# pihat.net
KiCad netlist of a schematic drawn in EAGLE
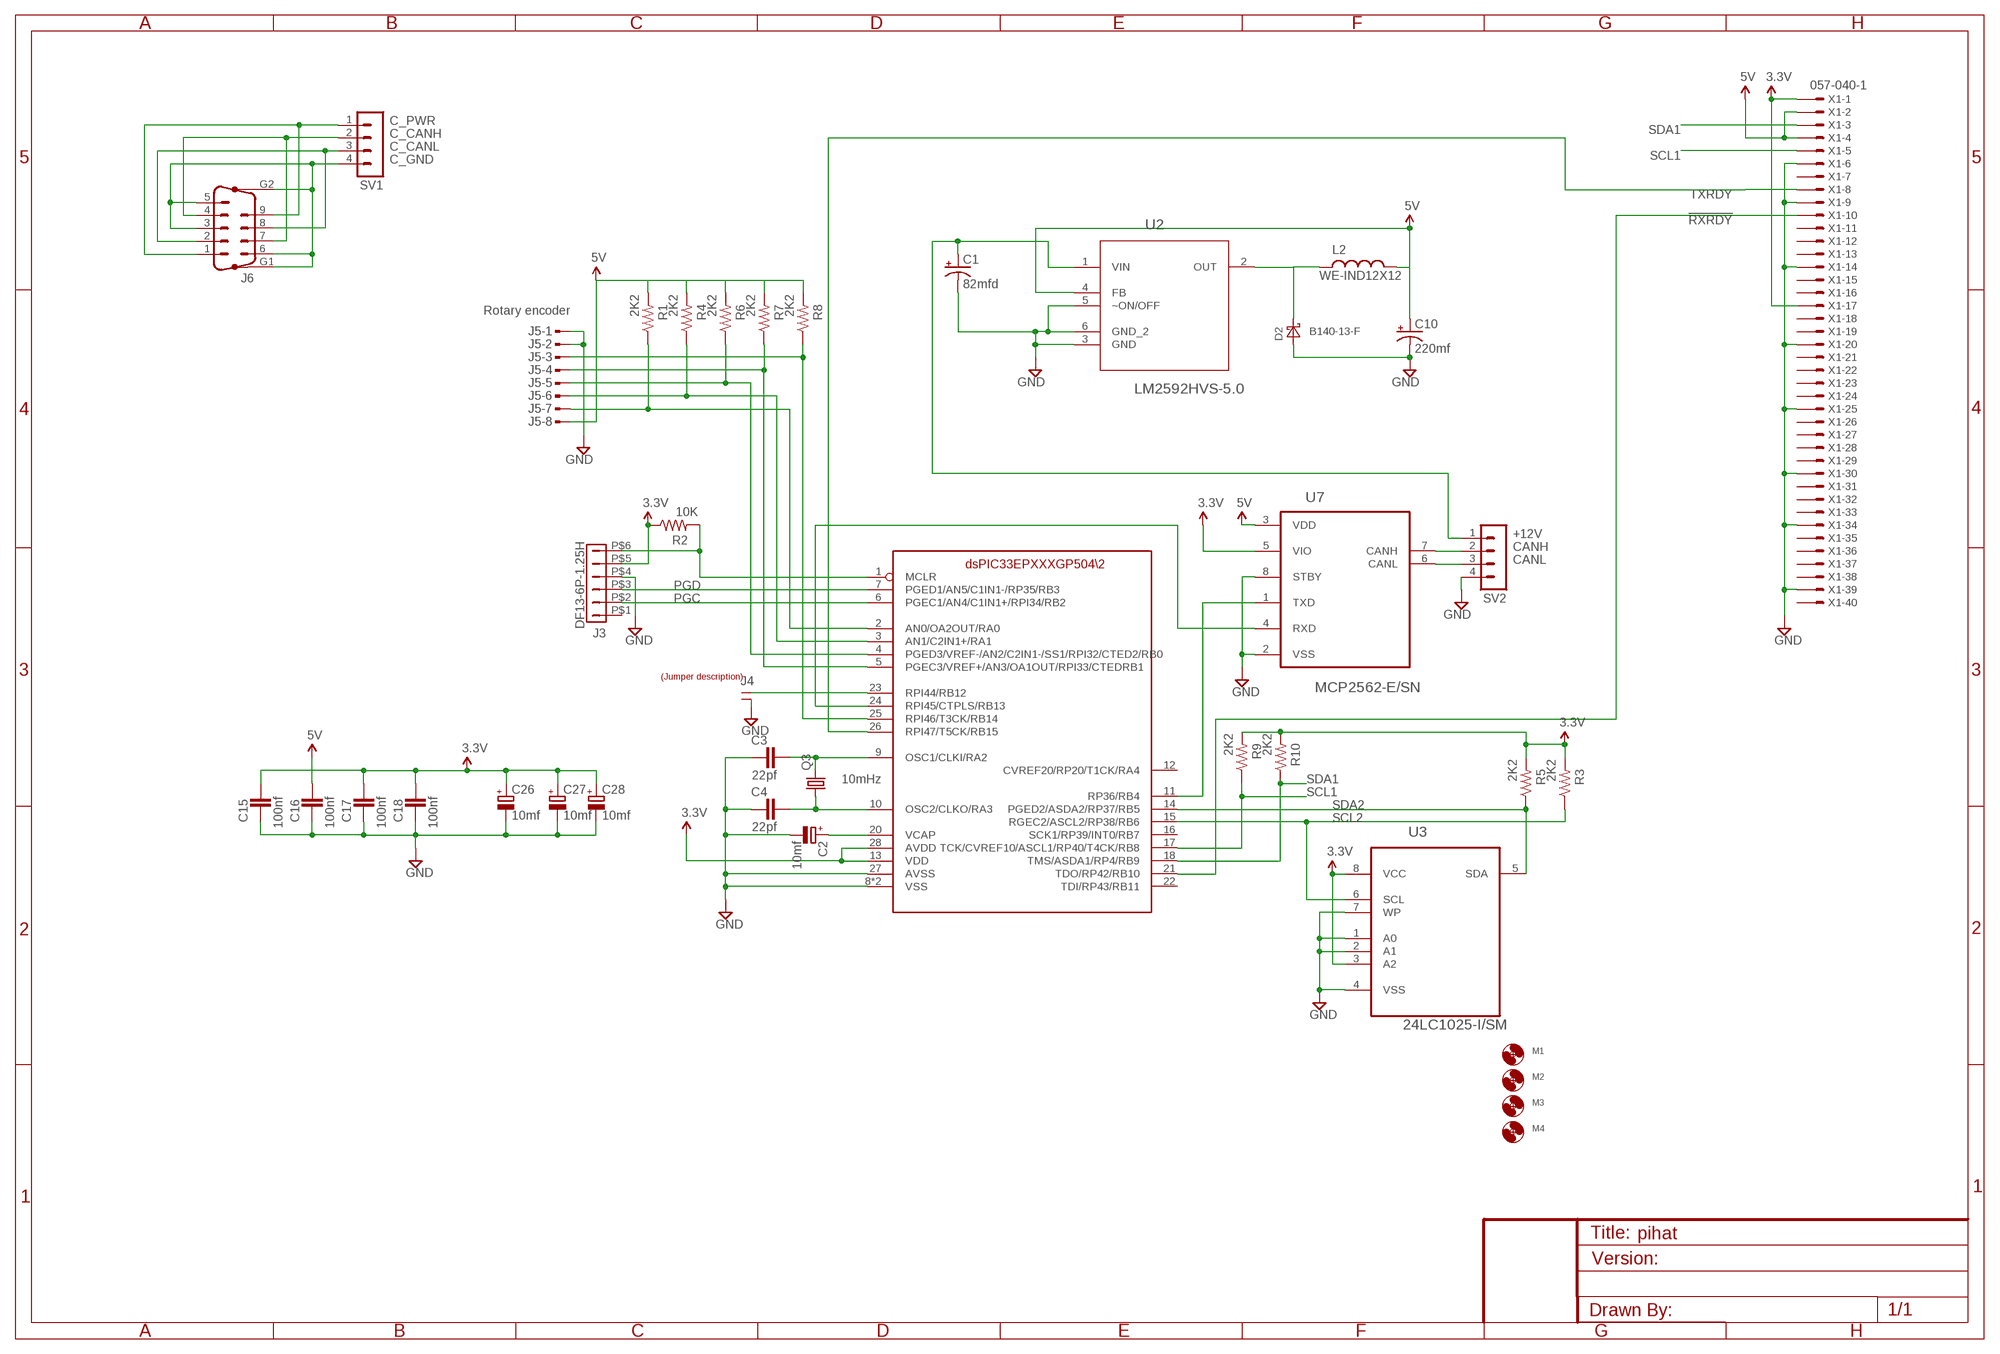
[diagram p0: schematic, sheet 1]

(export (version "E")
  (design (tool "Eeschema 10.0.6"))
  (components
    (comp (ref "C1")
      (value "82mfd")
      (footprint "eagle-import:SVPF-E7")
      (libsource (lib "eagle-import") (part "CAPACITOR_POL-SVPF-E7"))
    )
    (comp (ref "C2")
      (value "10mf")
      (footprint "eagle-import:SMC_A")
      (fields (field (name "PARTNO") "T491A106K004AT"))
      (libsource (lib "eagle-import") (part "CAPACITOR_POL-SMC_A"))
    )
    (comp (ref "C3")
      (value "22pf")
      (footprint "eagle-import:C805")
      (fields (field (name "PARTNO") "C0805C220J5GACTU"))
      (libsource (lib "eagle-import") (part "CAPACITOR_NPOL-0805"))
    )
    (comp (ref "C4")
      (value "22pf")
      (footprint "eagle-import:C805")
      (fields (field (name "PARTNO") "C0805C220J5GACTU"))
      (libsource (lib "eagle-import") (part "CAPACITOR_NPOL-0805"))
    )
    (comp (ref "C10")
      (value "220mf")
      (footprint "eagle-import:EIA7343")
      (fields (field (name "PARTNO") "T545X227M016ATE035"))
      (libsource (lib "eagle-import") (part "CAP_POL7343"))
    )
    (comp (ref "C15")
      (value "100nf")
      (footprint "eagle-import:C805")
      (fields (field (name "PARTNO") "CL21F104ZBCNNNC"))
      (libsource (lib "eagle-import") (part "CAPACITOR_NPOL-0805"))
    )
    (comp (ref "C16")
      (value "100nf")
      (footprint "eagle-import:C805")
      (fields (field (name "PARTNO") "CL21F104ZBCNNNC"))
      (libsource (lib "eagle-import") (part "CAPACITOR_NPOL-0805"))
    )
    (comp (ref "C17")
      (value "100nf")
      (footprint "eagle-import:C805")
      (fields (field (name "PARTNO") "CL21F104ZBCNNNC"))
      (libsource (lib "eagle-import") (part "CAPACITOR_NPOL-0805"))
    )
    (comp (ref "C18")
      (value "100nf")
      (footprint "eagle-import:C805")
      (fields (field (name "PARTNO") "CL21F104ZBCNNNC"))
      (libsource (lib "eagle-import") (part "CAPACITOR_NPOL-0805"))
    )
    (comp (ref "C26")
      (value "10mf")
      (footprint "eagle-import:SMC_A")
      (fields (field (name "PARTNO") "T491A106K004AT"))
      (libsource (lib "eagle-import") (part "CAPACITOR_POL-SMC_A"))
    )
    (comp (ref "C27")
      (value "10mf")
      (footprint "eagle-import:SMC_A")
      (fields (field (name "PARTNO") "T491A106K004AT"))
      (libsource (lib "eagle-import") (part "CAPACITOR_POL-SMC_A"))
    )
    (comp (ref "C28")
      (value "10mf")
      (footprint "eagle-import:SMC_A")
      (fields (field (name "PARTNO") "T491A106K004AT"))
      (libsource (lib "eagle-import") (part "CAPACITOR_POL-SMC_A"))
    )
    (comp (ref "D2")
      (value "B140-13-F")
      (footprint "eagle-import:SMA")
      (libsource (lib "eagle-import") (part "DIODE-SCHOTTKY-SMA"))
    )
    (comp (ref "J3")
      (value "DF13-6P-1.25H")
      (footprint "eagle-import:DF13A-6P-1.25H")
      (fields (field (name "PARTNO") "DF13A-6P-1.25H(20)"))
      (libsource (lib "eagle-import") (part "DF13-6P-1.25H"))
    )
    (comp (ref "J4")
      (value "JUMPER-1X2")
      (footprint "eagle-import:JUMPER-1X2")
      (fields (field (name "PARTNO") "M20-9770246"))
      (libsource (lib "eagle-import") (part "JUMPER-1X2"))
    )
    (comp (ref "J5")
      (value "MTOP-8")
      (footprint "eagle-import:MTOP-8")
      (fields (field (name "PARTNO") "7-215079-8"))
      (libsource (lib "eagle-import") (part "MTOP-8"))
    )
    (comp (ref "J6")
      (value "M09VP")
      (footprint "eagle-import:M09VP")
      (libsource (lib "eagle-import") (part "M09VP"))
    )
    (comp (ref "L2")
      (value "WE-IND12X12")
      (footprint "eagle-import:IND12X12")
      (libsource (lib "eagle-import") (part "WE-IND12X12"))
    )
    (comp (ref "M1")
      (value "MOUNT-HOLE2.8")
      (footprint "eagle-import:2,8")
      (libsource (lib "eagle-import") (part "MOUNT-HOLE2.8"))
    )
    (comp (ref "M2")
      (value "MOUNT-HOLE2.8")
      (footprint "eagle-import:2,8")
      (libsource (lib "eagle-import") (part "MOUNT-HOLE2.8"))
    )
    (comp (ref "M3")
      (value "MOUNT-HOLE2.8")
      (footprint "eagle-import:2,8")
      (libsource (lib "eagle-import") (part "MOUNT-HOLE2.8"))
    )
    (comp (ref "M4")
      (value "MOUNT-HOLE2.8")
      (footprint "eagle-import:2,8")
      (libsource (lib "eagle-import") (part "MOUNT-HOLE2.8"))
    )
    (comp (ref "Q3")
      (value "10mHz")
      (footprint "eagle-import:HC49_S")
      (fields (field (name "PARTNO") "ATS100B-E"))
      (libsource (lib "eagle-import") (part "CRYSTALHC49S"))
    )
    (comp (ref "R1")
      (value "2K2")
      (footprint "eagle-import:0603-RES")
      (fields (field (name "PARTNO") "RC0603FR-072K2L"))
      (libsource (lib "eagle-import") (part "RESISTOR0603-RES"))
    )
    (comp (ref "R2")
      (value "10K")
      (footprint "eagle-import:0603-RES")
      (fields (field (name "PARTNO") "RC0603FR-0710KL"))
      (libsource (lib "eagle-import") (part "RESISTOR0603-RES"))
    )
    (comp (ref "R3")
      (value "2K2")
      (footprint "eagle-import:0603-RES")
      (fields (field (name "PARTNO") "RC0603FR-072K2L"))
      (libsource (lib "eagle-import") (part "RESISTOR0603-RES"))
    )
    (comp (ref "R4")
      (value "2K2")
      (footprint "eagle-import:0603-RES")
      (fields (field (name "PARTNO") "RC0603FR-072K2L"))
      (libsource (lib "eagle-import") (part "RESISTOR0603-RES"))
    )
    (comp (ref "R5")
      (value "2K2")
      (footprint "eagle-import:0603-RES")
      (fields (field (name "PARTNO") "RC0603FR-072K2L"))
      (libsource (lib "eagle-import") (part "RESISTOR0603-RES"))
    )
    (comp (ref "R6")
      (value "2K2")
      (footprint "eagle-import:0603-RES")
      (fields (field (name "PARTNO") "RC0603FR-072K2L"))
      (libsource (lib "eagle-import") (part "RESISTOR0603-RES"))
    )
    (comp (ref "R7")
      (value "2K2")
      (footprint "eagle-import:0603-RES")
      (fields (field (name "PARTNO") "RC0603FR-072K2L"))
      (libsource (lib "eagle-import") (part "RESISTOR0603-RES"))
    )
    (comp (ref "R8")
      (value "2K2")
      (footprint "eagle-import:0603-RES")
      (fields (field (name "PARTNO") "RC0603FR-072K2L"))
      (libsource (lib "eagle-import") (part "RESISTOR0603-RES"))
    )
    (comp (ref "R9")
      (value "2K2")
      (footprint "eagle-import:0603-RES")
      (fields (field (name "PARTNO") "RC0603FR-072K2L"))
      (libsource (lib "eagle-import") (part "RESISTOR0603-RES"))
    )
    (comp (ref "R10")
      (value "2K2")
      (footprint "eagle-import:0603-RES")
      (fields (field (name "PARTNO") "RC0603FR-072K2L"))
      (libsource (lib "eagle-import") (part "RESISTOR0603-RES"))
    )
    (comp (ref "SV1")
      (value "MA04-1")
      (footprint "eagle-import:MA04-1")
      (libsource (lib "eagle-import") (part "MA04-1"))
    )
    (comp (ref "SV2")
      (value "MA04-1")
      (footprint "eagle-import:MA04-1")
      (libsource (lib "eagle-import") (part "MA04-1"))
    )
    (comp (ref "U$1")
      (value "LABEL_JUMPER_1X2")
      (footprint "eagle-import:JUMP2_DESC")
      (fields (field (name "OFF") "Normal") (field (name "ON") "Reset"))
      (libsource (lib "eagle-import") (part "LABEL_JUMPER_1X2"))
    )
    (comp (ref "U2")
      (value "LM2592HVS-5.0")
      (footprint "eagle-import:TO170P1435X457-5N")
      (fields (field (name "PARTNO") "LM2592HVSX-5.0/NOPB"))
      (libsource (lib "eagle-import") (part "LM2592HVS-5.0"))
    )
    (comp (ref "U3")
      (value "24LC1025-I/SM")
      (footprint "eagle-import:SOIC8-N_MC")
      (fields (field (name "PARTNO") "24LC1025T-I/SN"))
      (libsource (lib "eagle-import") (part "24LC1025-I/SM"))
    )
    (comp (ref "U4")
      (value "DSPIC33EPXXXGP502")
      (footprint "eagle-import:SOIC-28")
      (libsource (lib "eagle-import") (part "DSPIC33EPXXXGP502"))
    )
    (comp (ref "U7")
      (value "MCP2562-E/SN")
      (footprint "eagle-import:SOIC-8N")
      (libsource (lib "eagle-import") (part "MCP2562-E/SN"))
    )
    (comp (ref "X1")
      (value "057-040-1")
      (footprint "eagle-import:057-040-1")
      (libsource (lib "eagle-import") (part "057-040-1"))
    )
  )
  (nets
    (net (code "1") (name "/+12V") (class "Default")
      (node (ref "C1") (pin "P$2") (pinfunction "+_P$2") (pintype "passive"))
      (node (ref "SV2") (pin "1") (pinfunction "1_1") (pintype "passive"))
      (node (ref "U2") (pin "1") (pinfunction "VIN_1") (pintype "power_in"))
    )
    (net (code "2") (name "/CANH") (class "Default")
      (node (ref "SV2") (pin "2") (pinfunction "2_2") (pintype "passive"))
      (node (ref "U7") (pin "7") (pinfunction "CANH_7") (pintype "bidirectional"))
    )
    (net (code "3") (name "/CANL") (class "Default")
      (node (ref "SV2") (pin "3") (pinfunction "3_3") (pintype "passive"))
      (node (ref "U7") (pin "6") (pinfunction "CANL_6") (pintype "bidirectional"))
    )
    (net (code "4") (name "/C_CANH") (class "Default")
      (node (ref "J6") (pin "4") (pinfunction "4_4") (pintype "passive"))
      (node (ref "J6") (pin "7") (pinfunction "7_7") (pintype "passive"))
      (node (ref "SV1") (pin "2") (pinfunction "2_2") (pintype "passive"))
    )
    (net (code "5") (name "/C_CANL") (class "Default")
      (node (ref "J6") (pin "2") (pinfunction "2_2") (pintype "passive"))
      (node (ref "J6") (pin "8") (pinfunction "8_8") (pintype "passive"))
      (node (ref "SV1") (pin "3") (pinfunction "3_3") (pintype "passive"))
    )
    (net (code "6") (name "/C_GND") (class "Default")
      (node (ref "J6") (pin "3") (pinfunction "3_3") (pintype "passive"))
      (node (ref "J6") (pin "5") (pinfunction "5_5") (pintype "passive"))
      (node (ref "J6") (pin "6") (pinfunction "6_6") (pintype "passive"))
      (node (ref "J6") (pin "G1") (pinfunction "G1_G1") (pintype "passive"))
      (node (ref "J6") (pin "G2") (pinfunction "G2_G2") (pintype "passive"))
      (node (ref "SV1") (pin "4") (pinfunction "4_4") (pintype "passive"))
    )
    (net (code "7") (name "/C_PWR") (class "Default")
      (node (ref "J6") (pin "1") (pinfunction "1_1") (pintype "passive"))
      (node (ref "J6") (pin "9") (pinfunction "9_9") (pintype "passive"))
      (node (ref "SV1") (pin "1") (pinfunction "1_1") (pintype "passive"))
    )
    (net (code "8") (name "/PGC") (class "Default")
      (node (ref "J3") (pin "P$2") (pinfunction "2_P$2") (pintype "passive"))
      (node (ref "U4") (pin "6") (pinfunction "PGEC1/AN4/C1IN1+/RPI34/RB2_6") (pintype "bidirectional"))
    )
    (net (code "9") (name "/PGD") (class "Default")
      (node (ref "J3") (pin "P$3") (pinfunction "3_P$3") (pintype "passive"))
      (node (ref "U4") (pin "7") (pinfunction "PGED1/AN5/C1IN1-/RP35/RB3_7") (pintype "bidirectional"))
    )
    (net (code "10") (name "/SCL1") (class "Default")
      (node (ref "R9") (pin "1") (pinfunction "1_1") (pintype "passive"))
      (node (ref "U4") (pin "17") (pinfunction "TCK/CVREF10/ASCL1/RP40/T4CK/RB8_17") (pintype "bidirectional"))
      (node (ref "X1") (pin "5") (pinfunction "S_5") (pintype "passive"))
    )
    (net (code "11") (name "/SCL2") (class "Default")
      (node (ref "R3") (pin "1") (pinfunction "1_1") (pintype "passive"))
      (node (ref "U3") (pin "6") (pinfunction "SCL_6") (pintype "input"))
      (node (ref "U4") (pin "15") (pinfunction "RGEC2/ASCL2/RP38/RB6_15") (pintype "bidirectional"))
    )
    (net (code "12") (name "/SDA1") (class "Default")
      (node (ref "R10") (pin "1") (pinfunction "1_1") (pintype "passive"))
      (node (ref "U4") (pin "18") (pinfunction "TMS/ASDA1/RP4/RB9_18") (pintype "bidirectional"))
      (node (ref "X1") (pin "3") (pinfunction "S_3") (pintype "passive"))
    )
    (net (code "13") (name "/SDA2") (class "Default")
      (node (ref "R5") (pin "1") (pinfunction "1_1") (pintype "passive"))
      (node (ref "U3") (pin "5") (pinfunction "SDA_5") (pintype "bidirectional"))
      (node (ref "U4") (pin "14") (pinfunction "PGED2/ASDA2/RP37/RB5_14") (pintype "bidirectional"))
    )
    (net (code "14") (name "/TXRDY") (class "Default")
      (node (ref "U4") (pin "26") (pinfunction "RPI47/T5CK/RB15_26") (pintype "bidirectional"))
      (node (ref "X1") (pin "8") (pinfunction "S_8") (pintype "passive"))
    )
    (net (code "15") (name "/~{RXRDY}") (class "Default")
      (node (ref "U4") (pin "21") (pinfunction "TDO/RP42/RB10_21") (pintype "bidirectional"))
      (node (ref "X1") (pin "10") (pinfunction "S_10") (pintype "passive"))
    )
    (net (code "16") (name "3.3V") (class "Default")
      (node (ref "C15") (pin "1") (pinfunction "1_1") (pintype "passive"))
      (node (ref "C17") (pin "1") (pinfunction "1_1") (pintype "passive"))
      (node (ref "C18") (pin "1") (pinfunction "1_1") (pintype "passive"))
      (node (ref "C26") (pin "+") (pinfunction "+_+") (pintype "passive"))
      (node (ref "C27") (pin "+") (pinfunction "+_+") (pintype "passive"))
      (node (ref "C28") (pin "+") (pinfunction "+_+") (pintype "passive"))
      (node (ref "J3") (pin "P$5") (pinfunction "5_P$5") (pintype "passive"))
      (node (ref "R10") (pin "2") (pinfunction "2_2") (pintype "passive"))
      (node (ref "R2") (pin "1") (pinfunction "1_1") (pintype "passive"))
      (node (ref "R3") (pin "2") (pinfunction "2_2") (pintype "passive"))
      (node (ref "R5") (pin "2") (pinfunction "2_2") (pintype "passive"))
      (node (ref "R9") (pin "2") (pinfunction "2_2") (pintype "passive"))
      (node (ref "U3") (pin "3") (pinfunction "A2_3") (pintype "input"))
      (node (ref "U3") (pin "8") (pinfunction "VCC_8") (pintype "power_in"))
      (node (ref "U4") (pin "13") (pinfunction "VDD_13") (pintype "bidirectional"))
      (node (ref "U4") (pin "28") (pinfunction "AVDD_28") (pintype "bidirectional"))
      (node (ref "U7") (pin "5") (pinfunction "VIO_5") (pintype "power_in"))
      (node (ref "X1") (pin "1") (pinfunction "S_1") (pintype "passive"))
      (node (ref "X1") (pin "17") (pinfunction "S_17") (pintype "passive"))
    )
    (net (code "17") (name "5V") (class "Default")
      (node (ref "C10") (pin "A") (pinfunction "+_A") (pintype "passive"))
      (node (ref "C16") (pin "1") (pinfunction "1_1") (pintype "passive"))
      (node (ref "J5") (pin "8") (pinfunction "1_8") (pintype "passive"))
      (node (ref "L2") (pin "P$2") (pinfunction "2_P$2") (pintype "passive"))
      (node (ref "R1") (pin "2") (pinfunction "2_2") (pintype "passive"))
      (node (ref "R4") (pin "2") (pinfunction "2_2") (pintype "passive"))
      (node (ref "R6") (pin "2") (pinfunction "2_2") (pintype "passive"))
      (node (ref "R7") (pin "2") (pinfunction "2_2") (pintype "passive"))
      (node (ref "R8") (pin "2") (pinfunction "2_2") (pintype "passive"))
      (node (ref "U2") (pin "4") (pinfunction "FB_4") (pintype "input"))
      (node (ref "U7") (pin "3") (pinfunction "VDD_3") (pintype "power_in"))
      (node (ref "X1") (pin "2") (pinfunction "S_2") (pintype "passive"))
      (node (ref "X1") (pin "4") (pinfunction "S_4") (pintype "passive"))
    )
    (net (code "18") (name "GND") (class "Default")
      (node (ref "C1") (pin "P$1") (pinfunction "-_P$1") (pintype "passive"))
      (node (ref "C10") (pin "C") (pinfunction "-_C") (pintype "passive"))
      (node (ref "C15") (pin "2") (pinfunction "2_2") (pintype "passive"))
      (node (ref "C16") (pin "2") (pinfunction "2_2") (pintype "passive"))
      (node (ref "C17") (pin "2") (pinfunction "2_2") (pintype "passive"))
      (node (ref "C18") (pin "2") (pinfunction "2_2") (pintype "passive"))
      (node (ref "C2") (pin "-") (pinfunction "-_-") (pintype "passive"))
      (node (ref "C26") (pin "-") (pinfunction "-_-") (pintype "passive"))
      (node (ref "C27") (pin "-") (pinfunction "-_-") (pintype "passive"))
      (node (ref "C28") (pin "-") (pinfunction "-_-") (pintype "passive"))
      (node (ref "C3") (pin "2") (pinfunction "2_2") (pintype "passive"))
      (node (ref "C4") (pin "2") (pinfunction "2_2") (pintype "passive"))
      (node (ref "D2") (pin "A") (pinfunction "A_A") (pintype "passive"))
      (node (ref "J3") (pin "P$4") (pinfunction "4_P$4") (pintype "passive"))
      (node (ref "J4") (pin "2") (pinfunction "2_2") (pintype "bidirectional"))
      (node (ref "J5") (pin "1") (pinfunction "1_1") (pintype "passive"))
      (node (ref "J5") (pin "2") (pinfunction "1_2") (pintype "passive"))
      (node (ref "SV2") (pin "4") (pinfunction "4_4") (pintype "passive"))
      (node (ref "U2") (pin "3") (pinfunction "GND_3") (pintype "passive"))
      (node (ref "U2") (pin "5") (pinfunction "~{ON/OFF}_5") (pintype "input"))
      (node (ref "U2") (pin "6") (pinfunction "GND_2_6") (pintype "passive"))
      (node (ref "U3") (pin "1") (pinfunction "A0_1") (pintype "input"))
      (node (ref "U3") (pin "2") (pinfunction "A1_2") (pintype "input"))
      (node (ref "U3") (pin "4") (pinfunction "VSS_4") (pintype "passive"))
      (node (ref "U3") (pin "7") (pinfunction "WP_7") (pintype "input"))
      (node (ref "U4") (pin "19") (pinfunction "VSS_19") (pintype "bidirectional"))
      (node (ref "U4") (pin "27") (pinfunction "AVSS_27") (pintype "bidirectional"))
      (node (ref "U4") (pin "8") (pinfunction "VSS_8") (pintype "bidirectional"))
      (node (ref "U7") (pin "2") (pinfunction "VSS_2") (pintype "power_in"))
      (node (ref "U7") (pin "8") (pinfunction "STBY_8") (pintype "input"))
      (node (ref "X1") (pin "14") (pinfunction "S_14") (pintype "passive"))
      (node (ref "X1") (pin "20") (pinfunction "S_20") (pintype "passive"))
      (node (ref "X1") (pin "25") (pinfunction "S_25") (pintype "passive"))
      (node (ref "X1") (pin "30") (pinfunction "S_30") (pintype "passive"))
      (node (ref "X1") (pin "34") (pinfunction "S_34") (pintype "passive"))
      (node (ref "X1") (pin "39") (pinfunction "S_39") (pintype "passive"))
      (node (ref "X1") (pin "6") (pinfunction "S_6") (pintype "passive"))
      (node (ref "X1") (pin "9") (pinfunction "S_9") (pintype "passive"))
    )
    (net (code "19") (name "Net-(J3-6)") (class "Default")
      (node (ref "J3") (pin "P$6") (pinfunction "6_P$6") (pintype "passive"))
      (node (ref "R2") (pin "2") (pinfunction "2_2") (pintype "passive"))
      (node (ref "U4") (pin "1") (pinfunction "MCLR_1") (pintype "input"))
    )
    (net (code "20") (name "Net-(J5C-1)") (class "Default")
      (node (ref "J5") (pin "3") (pinfunction "1_3") (pintype "passive"))
      (node (ref "R8") (pin "1") (pinfunction "1_1") (pintype "passive"))
      (node (ref "U4") (pin "25") (pinfunction "RPI46/T3CK/RB14_25") (pintype "bidirectional"))
    )
    (net (code "21") (name "Net-(J5D-1)") (class "Default")
      (node (ref "J5") (pin "4") (pinfunction "1_4") (pintype "passive"))
      (node (ref "R7") (pin "1") (pinfunction "1_1") (pintype "passive"))
      (node (ref "U4") (pin "5") (pinfunction "PGEC3/VREF+/AN3/OA1OUT/RPI33/CTEDRB1_5") (pintype "bidirectional"))
    )
    (net (code "22") (name "Net-(J5E-1)") (class "Default")
      (node (ref "J5") (pin "5") (pinfunction "1_5") (pintype "passive"))
      (node (ref "R6") (pin "1") (pinfunction "1_1") (pintype "passive"))
      (node (ref "U4") (pin "4") (pinfunction "PGED3/VREF-/AN2/C2IN1-/SS1/RPI32/CTED2/RB0_4") (pintype "bidirectional"))
    )
    (net (code "23") (name "Net-(J5F-1)") (class "Default")
      (node (ref "J5") (pin "6") (pinfunction "1_6") (pintype "passive"))
      (node (ref "R4") (pin "1") (pinfunction "1_1") (pintype "passive"))
      (node (ref "U4") (pin "3") (pinfunction "AN1/C2IN1+/RA1_3") (pintype "bidirectional"))
    )
    (net (code "24") (name "Net-(J5G-1)") (class "Default")
      (node (ref "J5") (pin "7") (pinfunction "1_7") (pintype "passive"))
      (node (ref "R1") (pin "1") (pinfunction "1_1") (pintype "passive"))
      (node (ref "U4") (pin "2") (pinfunction "AN0/OA2OUT/RA0_2") (pintype "bidirectional"))
    )
    (net (code "25") (name "Net-(L2-1)") (class "Default")
      (node (ref "D2") (pin "C") (pinfunction "C_C") (pintype "passive"))
      (node (ref "L2") (pin "P$1") (pinfunction "1_P$1") (pintype "passive"))
      (node (ref "U2") (pin "2") (pinfunction "OUT_2") (pintype "output"))
    )
    (net (code "26") (name "Net-(U4-OSC1{slash}CLKI{slash}RA2)") (class "Default")
      (node (ref "C3") (pin "1") (pinfunction "1_1") (pintype "passive"))
      (node (ref "Q3") (pin "2") (pinfunction "2_2") (pintype "passive"))
      (node (ref "U4") (pin "9") (pinfunction "OSC1/CLKI/RA2_9") (pintype "bidirectional"))
    )
    (net (code "27") (name "Net-(U4-OSC2{slash}CLKO{slash}RA3)") (class "Default")
      (node (ref "C4") (pin "1") (pinfunction "1_1") (pintype "passive"))
      (node (ref "Q3") (pin "1") (pinfunction "1_1") (pintype "passive"))
      (node (ref "U4") (pin "10") (pinfunction "OSC2/CLKO/RA3_10") (pintype "bidirectional"))
    )
    (net (code "28") (name "Net-(U4-RP36{slash}RB4)") (class "Default")
      (node (ref "U4") (pin "11") (pinfunction "RP36/RB4_11") (pintype "bidirectional"))
      (node (ref "U7") (pin "1") (pinfunction "TXD_1") (pintype "input"))
    )
    (net (code "29") (name "Net-(U4-RPI44{slash}RB12)") (class "Default")
      (node (ref "J4") (pin "1") (pinfunction "1_1") (pintype "bidirectional"))
      (node (ref "U4") (pin "23") (pinfunction "RPI44/RB12_23") (pintype "bidirectional"))
    )
    (net (code "30") (name "Net-(U4-RPI45{slash}CTPLS{slash}RB13)") (class "Default")
      (node (ref "U4") (pin "24") (pinfunction "RPI45/CTPLS/RB13_24") (pintype "bidirectional"))
      (node (ref "U7") (pin "4") (pinfunction "RXD_4") (pintype "output"))
    )
    (net (code "31") (name "Net-(U4-VCAP)") (class "Default")
      (node (ref "C2") (pin "+") (pinfunction "+_+") (pintype "passive"))
      (node (ref "U4") (pin "20") (pinfunction "VCAP_20") (pintype "bidirectional"))
    )
    (net (code "32") (name "unconnected-(J3-1-PadP$1)") (class "Default")
      (node (ref "J3") (pin "P$1") (pinfunction "1_P$1") (pintype "passive"))
    )
    (net (code "33") (name "unconnected-(U4-CVREF20{slash}RP20{slash}T1CK{slash}RA4-Pad12)") (class "Default")
      (node (ref "U4") (pin "12") (pinfunction "CVREF20/RP20/T1CK/RA4_12") (pintype "bidirectional"))
    )
    (net (code "34") (name "unconnected-(U4-SCK1{slash}RP39{slash}INT0{slash}RB7-Pad16)") (class "Default")
      (node (ref "U4") (pin "16") (pinfunction "SCK1/RP39/INT0/RB7_16") (pintype "bidirectional"))
    )
    (net (code "35") (name "unconnected-(U4-TDI{slash}RP43{slash}RB11-Pad22)") (class "Default")
      (node (ref "U4") (pin "22") (pinfunction "TDI/RP43/RB11_22") (pintype "bidirectional"))
    )
    (net (code "36") (name "unconnected-(X1AA-S-Pad33)") (class "Default")
      (node (ref "X1") (pin "33") (pinfunction "S_33") (pintype "passive"))
    )
    (net (code "37") (name "unconnected-(X1AC-S-Pad35)") (class "Default")
      (node (ref "X1") (pin "35") (pinfunction "S_35") (pintype "passive"))
    )
    (net (code "38") (name "unconnected-(X1AD-S-Pad36)") (class "Default")
      (node (ref "X1") (pin "36") (pinfunction "S_36") (pintype "passive"))
    )
    (net (code "39") (name "unconnected-(X1AE-S-Pad37)") (class "Default")
      (node (ref "X1") (pin "37") (pinfunction "S_37") (pintype "passive"))
    )
    (net (code "40") (name "unconnected-(X1AF-S-Pad38)") (class "Default")
      (node (ref "X1") (pin "38") (pinfunction "S_38") (pintype "passive"))
    )
    (net (code "41") (name "unconnected-(X1AI-S-Pad40)") (class "Default")
      (node (ref "X1") (pin "40") (pinfunction "S_40") (pintype "passive"))
    )
    (net (code "42") (name "unconnected-(X1AL-S-Pad7)") (class "Default")
      (node (ref "X1") (pin "7") (pinfunction "S_7") (pintype "passive"))
    )
    (net (code "43") (name "unconnected-(X1C-S-Pad11)") (class "Default")
      (node (ref "X1") (pin "11") (pinfunction "S_11") (pintype "passive"))
    )
    (net (code "44") (name "unconnected-(X1D-S-Pad12)") (class "Default")
      (node (ref "X1") (pin "12") (pinfunction "S_12") (pintype "passive"))
    )
    (net (code "45") (name "unconnected-(X1E-S-Pad13)") (class "Default")
      (node (ref "X1") (pin "13") (pinfunction "S_13") (pintype "passive"))
    )
    (net (code "46") (name "unconnected-(X1G-S-Pad15)") (class "Default")
      (node (ref "X1") (pin "15") (pinfunction "S_15") (pintype "passive"))
    )
    (net (code "47") (name "unconnected-(X1H-S-Pad16)") (class "Default")
      (node (ref "X1") (pin "16") (pinfunction "S_16") (pintype "passive"))
    )
    (net (code "48") (name "unconnected-(X1J-S-Pad18)") (class "Default")
      (node (ref "X1") (pin "18") (pinfunction "S_18") (pintype "passive"))
    )
    (net (code "49") (name "unconnected-(X1K-S-Pad19)") (class "Default")
      (node (ref "X1") (pin "19") (pinfunction "S_19") (pintype "passive"))
    )
    (net (code "50") (name "unconnected-(X1N-S-Pad21)") (class "Default")
      (node (ref "X1") (pin "21") (pinfunction "S_21") (pintype "passive"))
    )
    (net (code "51") (name "unconnected-(X1O-S-Pad22)") (class "Default")
      (node (ref "X1") (pin "22") (pinfunction "S_22") (pintype "passive"))
    )
    (net (code "52") (name "unconnected-(X1P-S-Pad23)") (class "Default")
      (node (ref "X1") (pin "23") (pinfunction "S_23") (pintype "passive"))
    )
    (net (code "53") (name "unconnected-(X1Q-S-Pad24)") (class "Default")
      (node (ref "X1") (pin "24") (pinfunction "S_24") (pintype "passive"))
    )
    (net (code "54") (name "unconnected-(X1S-S-Pad26)") (class "Default")
      (node (ref "X1") (pin "26") (pinfunction "S_26") (pintype "passive"))
    )
    (net (code "55") (name "unconnected-(X1T-S-Pad27)") (class "Default")
      (node (ref "X1") (pin "27") (pinfunction "S_27") (pintype "passive"))
    )
    (net (code "56") (name "unconnected-(X1U-S-Pad28)") (class "Default")
      (node (ref "X1") (pin "28") (pinfunction "S_28") (pintype "passive"))
    )
    (net (code "57") (name "unconnected-(X1V-S-Pad29)") (class "Default")
      (node (ref "X1") (pin "29") (pinfunction "S_29") (pintype "passive"))
    )
    (net (code "58") (name "unconnected-(X1Y-S-Pad31)") (class "Default")
      (node (ref "X1") (pin "31") (pinfunction "S_31") (pintype "passive"))
    )
    (net (code "59") (name "unconnected-(X1Z-S-Pad32)") (class "Default")
      (node (ref "X1") (pin "32") (pinfunction "S_32") (pintype "passive"))
    )
  )
)
